# WiFiRadio.net
KiCad netlist of a schematic drawn in EAGLE
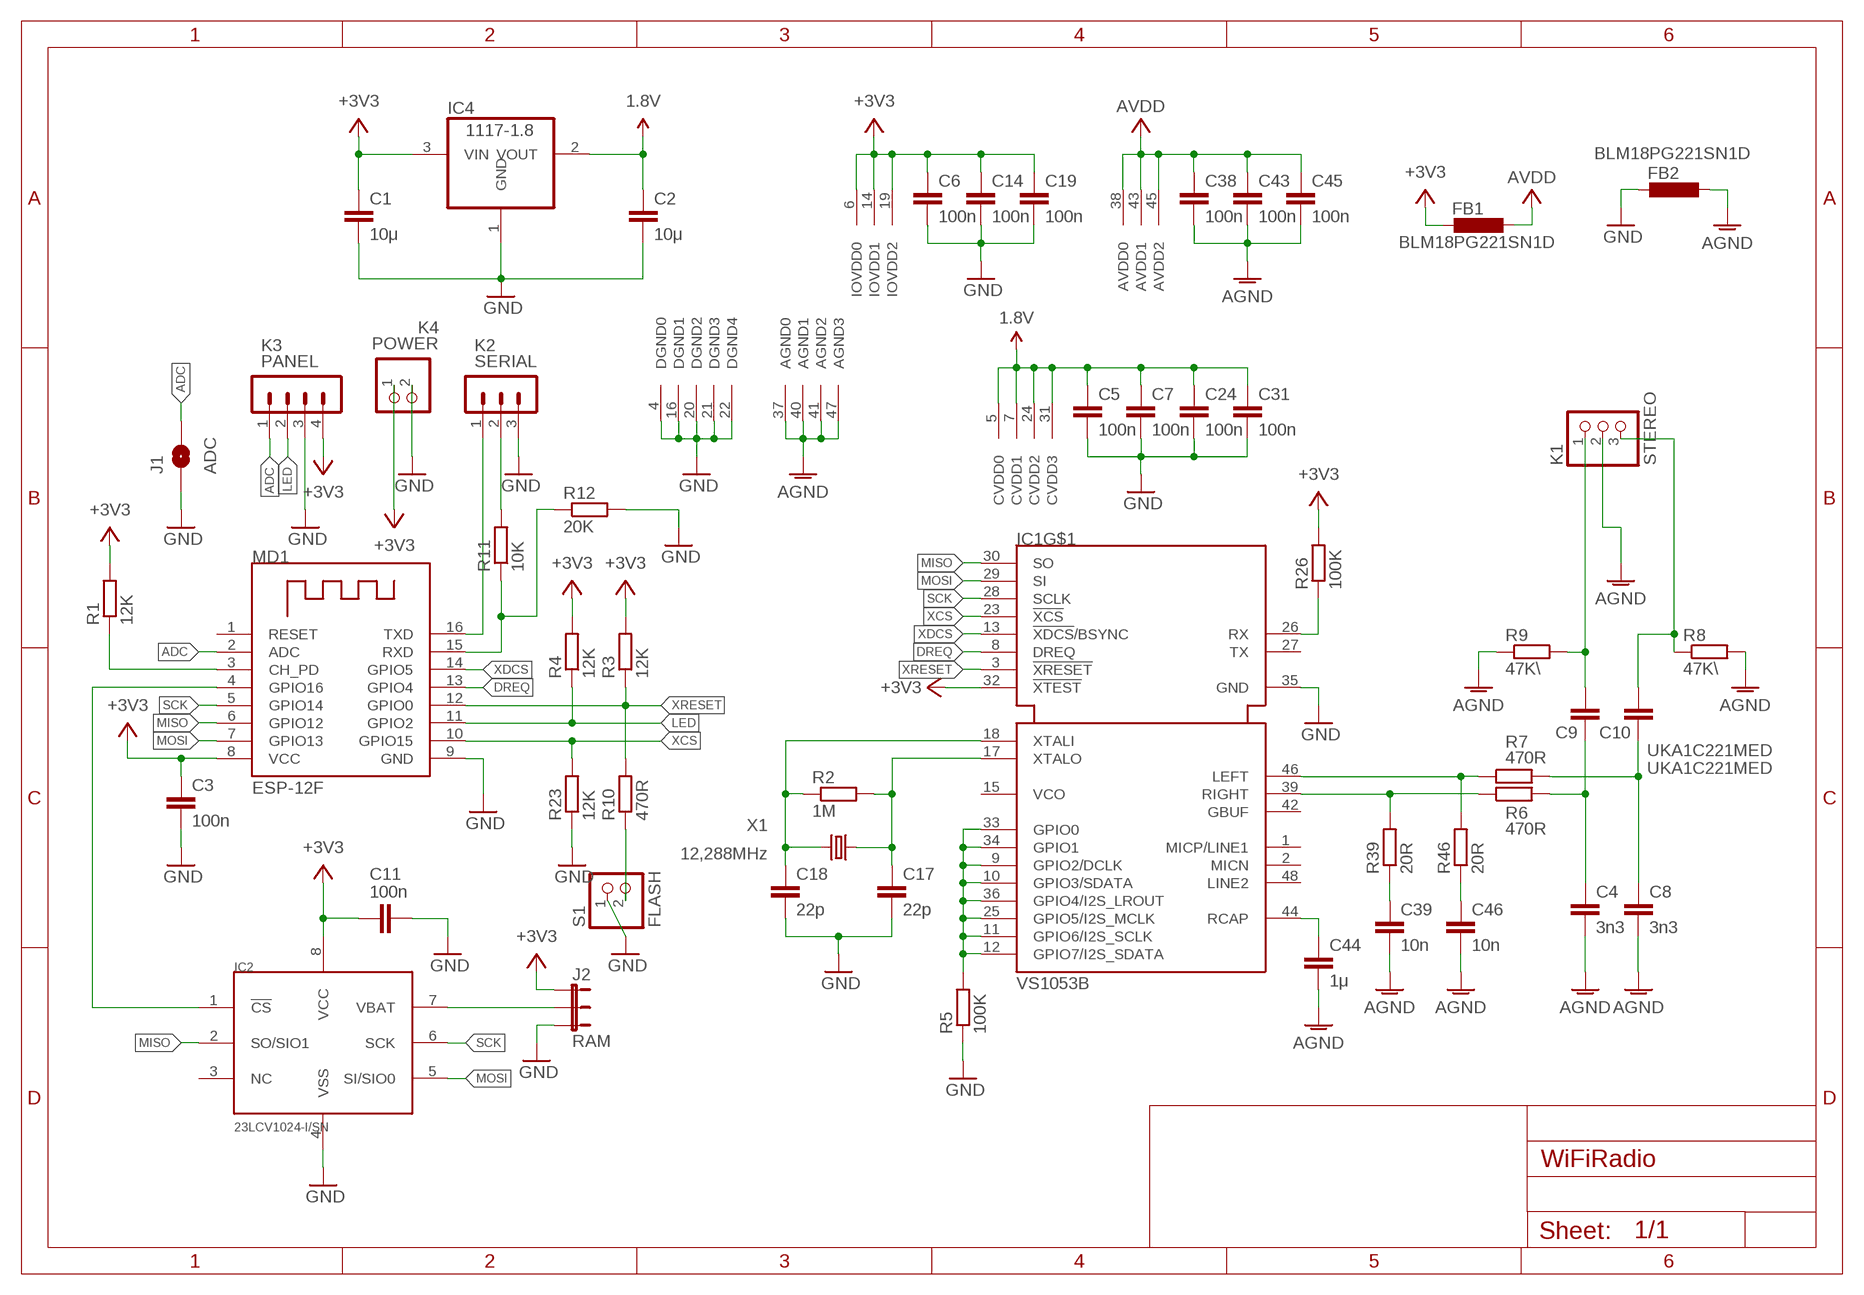
[diagram p0: schematic, sheet 1]

(export (version "E")
  (design (tool "Eeschema 10.0.6"))
  (components
    (comp (ref "C1")
      (value "10μ")
      (footprint "eagle-import:C0805")
      (libsource (lib "eagle-import") (part "C-EUC0805"))
    )
    (comp (ref "C2")
      (value "10μ")
      (footprint "eagle-import:C0805")
      (libsource (lib "eagle-import") (part "C-EUC0805"))
    )
    (comp (ref "C3")
      (value "100n")
      (footprint "eagle-import:C0603")
      (libsource (lib "eagle-import") (part "C-EUC0603"))
    )
    (comp (ref "C4")
      (value "3n3")
      (footprint "eagle-import:C0805")
      (libsource (lib "eagle-import") (part "C-EUC0805"))
    )
    (comp (ref "C5")
      (value "100n")
      (footprint "eagle-import:C0603")
      (libsource (lib "eagle-import") (part "C-EUC0603"))
    )
    (comp (ref "C6")
      (value "100n")
      (footprint "eagle-import:C0603")
      (libsource (lib "eagle-import") (part "C-EUC0603"))
    )
    (comp (ref "C7")
      (value "100n")
      (footprint "eagle-import:C0603")
      (libsource (lib "eagle-import") (part "C-EUC0603"))
    )
    (comp (ref "C8")
      (value "3n3")
      (footprint "eagle-import:C0805")
      (libsource (lib "eagle-import") (part "C-EUC0805"))
    )
    (comp (ref "C9")
      (value "UKA1C221MED")
      (footprint "eagle-import:C0805")
      (libsource (lib "eagle-import") (part "C-EUC0805"))
    )
    (comp (ref "C10")
      (value "UKA1C221MED")
      (footprint "eagle-import:C0805")
      (libsource (lib "eagle-import") (part "C-EUC0805"))
    )
    (comp (ref "C11")
      (value "100n")
      (footprint "eagle-import:C0603")
      (libsource (lib "eagle-import") (part "C-EUC0603"))
    )
    (comp (ref "C14")
      (value "100n")
      (footprint "eagle-import:C0603")
      (libsource (lib "eagle-import") (part "C-EUC0603"))
    )
    (comp (ref "C17")
      (value "22p")
      (footprint "eagle-import:C0805")
      (libsource (lib "eagle-import") (part "C-EUC0805"))
    )
    (comp (ref "C18")
      (value "22p")
      (footprint "eagle-import:C0805")
      (libsource (lib "eagle-import") (part "C-EUC0805"))
    )
    (comp (ref "C19")
      (value "100n")
      (footprint "eagle-import:C0603")
      (libsource (lib "eagle-import") (part "C-EUC0603"))
    )
    (comp (ref "C24")
      (value "100n")
      (footprint "eagle-import:C0603")
      (libsource (lib "eagle-import") (part "C-EUC0603"))
    )
    (comp (ref "C31")
      (value "100n")
      (footprint "eagle-import:C0603")
      (libsource (lib "eagle-import") (part "C-EUC0603"))
    )
    (comp (ref "C38")
      (value "100n")
      (footprint "eagle-import:C0603")
      (libsource (lib "eagle-import") (part "C-EUC0603"))
    )
    (comp (ref "C39")
      (value "10n")
      (footprint "eagle-import:C0805")
      (libsource (lib "eagle-import") (part "C-EUC0805"))
    )
    (comp (ref "C43")
      (value "100n")
      (footprint "eagle-import:C0603")
      (libsource (lib "eagle-import") (part "C-EUC0603"))
    )
    (comp (ref "C44")
      (value "1μ")
      (footprint "eagle-import:C0805")
      (libsource (lib "eagle-import") (part "C-EUC0805"))
    )
    (comp (ref "C45")
      (value "100n")
      (footprint "eagle-import:C0603")
      (libsource (lib "eagle-import") (part "C-EUC0603"))
    )
    (comp (ref "C46")
      (value "10n")
      (footprint "eagle-import:C0805")
      (libsource (lib "eagle-import") (part "C-EUC0805"))
    )
    (comp (ref "FB1")
      (value "BLM18PG221SN1D")
      (footprint "eagle-import:L2012C")
      (libsource (lib "eagle-import") (part "L-EUL2012C"))
    )
    (comp (ref "FB2")
      (value "BLM18PG221SN1D")
      (footprint "eagle-import:L2012C")
      (libsource (lib "eagle-import") (part "L-EUL2012C"))
    )
    (comp (ref "IC1")
      (value "VS1053B")
      (footprint "eagle-import:LQFP48")
      (libsource (lib "eagle-import") (part "VS1053B"))
    )
    (comp (ref "IC2")
      (value "23LCV1024-I/SN")
      (footprint "eagle-import:SO-08")
      (libsource (lib "eagle-import") (part "23LCV1024-I/SN"))
    )
    (comp (ref "IC4")
      (value "1117-1.8")
      (footprint "eagle-import:SOT223")
      (fields (field (name "MPN") "REG1117"))
      (libsource (lib "eagle-import") (part "REG1117"))
    )
    (comp (ref "J1")
      (value "ADC")
      (footprint "eagle-import:SJ_2S")
      (libsource (lib "eagle-import") (part "SOLDERJUMPER-OLDNC"))
    )
    (comp (ref "J2")
      (value "RAM")
      (footprint "eagle-import:SJ_3")
      (libsource (lib "eagle-import") (part "JUMPER-3SMD"))
    )
    (comp (ref "K1")
      (value "STEREO")
      (footprint "eagle-import:1X03")
      (libsource (lib "eagle-import") (part "PINHD-1X3"))
    )
    (comp (ref "K2")
      (value "SERIAL")
      (footprint "eagle-import:MA03-1")
      (libsource (lib "eagle-import") (part "MA03-1"))
    )
    (comp (ref "K3")
      (value "PANEL")
      (footprint "eagle-import:MA04-1")
      (libsource (lib "eagle-import") (part "MA04-1"))
    )
    (comp (ref "K4")
      (value "POWER")
      (footprint "eagle-import:1X02")
      (libsource (lib "eagle-import") (part "PINHD-1X2"))
    )
    (comp (ref "MD1")
      (value "ESP-12F")
      (footprint "eagle-import:ESP-12F")
      (libsource (lib "eagle-import") (part "ESP-12F"))
    )
    (comp (ref "R1")
      (value "12K")
      (footprint "eagle-import:R0805")
      (libsource (lib "eagle-import") (part "R-EU_R0805"))
    )
    (comp (ref "R2")
      (value "1M")
      (footprint "eagle-import:R0805")
      (libsource (lib "eagle-import") (part "R-EU_R0805"))
    )
    (comp (ref "R3")
      (value "12K")
      (footprint "eagle-import:R0805")
      (libsource (lib "eagle-import") (part "R-EU_R0805"))
    )
    (comp (ref "R4")
      (value "12K")
      (footprint "eagle-import:R0805")
      (libsource (lib "eagle-import") (part "R-EU_R0805"))
    )
    (comp (ref "R5")
      (value "100K")
      (footprint "eagle-import:R0805")
      (libsource (lib "eagle-import") (part "R-EU_R0805"))
    )
    (comp (ref "R6")
      (value "470R")
      (footprint "eagle-import:R0805")
      (libsource (lib "eagle-import") (part "R-EU_R0805"))
    )
    (comp (ref "R7")
      (value "470R")
      (footprint "eagle-import:R0805")
      (libsource (lib "eagle-import") (part "R-EU_R0805"))
    )
    (comp (ref "R8")
      (value "47K\\")
      (footprint "eagle-import:R0805")
      (libsource (lib "eagle-import") (part "R-EU_R0805"))
    )
    (comp (ref "R9")
      (value "47K\\")
      (footprint "eagle-import:R0805")
      (libsource (lib "eagle-import") (part "R-EU_R0805"))
    )
    (comp (ref "R10")
      (value "470R")
      (footprint "eagle-import:R0805")
      (libsource (lib "eagle-import") (part "R-EU_R0805"))
    )
    (comp (ref "R11")
      (value "10K")
      (footprint "eagle-import:R0603")
      (libsource (lib "eagle-import") (part "R-EU_R0603"))
    )
    (comp (ref "R12")
      (value "20K")
      (footprint "eagle-import:R0603")
      (libsource (lib "eagle-import") (part "R-EU_R0603"))
    )
    (comp (ref "R23")
      (value "12K")
      (footprint "eagle-import:R0805")
      (libsource (lib "eagle-import") (part "R-EU_R0805"))
    )
    (comp (ref "R26")
      (value "100K")
      (footprint "eagle-import:R0805")
      (libsource (lib "eagle-import") (part "R-EU_R0805"))
    )
    (comp (ref "R39")
      (value "20R")
      (footprint "eagle-import:R0805")
      (libsource (lib "eagle-import") (part "R-EU_R0805"))
    )
    (comp (ref "R46")
      (value "20R")
      (footprint "eagle-import:R0805")
      (libsource (lib "eagle-import") (part "R-EU_R0805"))
    )
    (comp (ref "S1")
      (value "FLASH")
      (footprint "eagle-import:1X02")
      (libsource (lib "eagle-import") (part "PINHD-1X2"))
    )
    (comp (ref "X1")
      (value "12,288MHz")
      (footprint "eagle-import:HC49_S")
      (libsource (lib "eagle-import") (part "CRYSTALHC49S"))
    )
  )
  (nets
    (net (code "1") (name "+3V3") (class "Default")
      (node (ref "C1") (pin "1") (pinfunction "1_1") (pintype "passive"))
      (node (ref "C11") (pin "1") (pinfunction "1_1") (pintype "passive"))
      (node (ref "C14") (pin "1") (pinfunction "1_1") (pintype "passive"))
      (node (ref "C19") (pin "1") (pinfunction "1_1") (pintype "passive"))
      (node (ref "C3") (pin "1") (pinfunction "1_1") (pintype "passive"))
      (node (ref "C6") (pin "1") (pinfunction "1_1") (pintype "passive"))
      (node (ref "FB1") (pin "2") (pinfunction "2_2") (pintype "passive"))
      (node (ref "IC1") (pin "14") (pinfunction "IOVDD1_14") (pintype "power_in"))
      (node (ref "IC1") (pin "19") (pinfunction "IOVDD2_19") (pintype "power_in"))
      (node (ref "IC1") (pin "32") (pinfunction "~{XTEST}_32") (pintype "input"))
      (node (ref "IC1") (pin "6") (pinfunction "IOVDD0_6") (pintype "power_in"))
      (node (ref "IC2") (pin "8") (pinfunction "VCC_8") (pintype "power_in"))
      (node (ref "IC4") (pin "3") (pinfunction "VIN_3") (pintype "input"))
      (node (ref "J2") (pin "1") (pinfunction "1_1") (pintype "passive"))
      (node (ref "K3") (pin "4") (pinfunction "4_4") (pintype "passive"))
      (node (ref "K4") (pin "1") (pinfunction "1_1") (pintype "passive"))
      (node (ref "MD1") (pin "8") (pinfunction "VCC_8") (pintype "power_in"))
      (node (ref "R1") (pin "2") (pinfunction "2_2") (pintype "passive"))
      (node (ref "R26") (pin "2") (pinfunction "2_2") (pintype "passive"))
      (node (ref "R3") (pin "2") (pinfunction "2_2") (pintype "passive"))
      (node (ref "R4") (pin "2") (pinfunction "2_2") (pintype "passive"))
    )
    (net (code "2") (name "1.8V") (class "Default")
      (node (ref "C2") (pin "1") (pinfunction "1_1") (pintype "passive"))
      (node (ref "C24") (pin "1") (pinfunction "1_1") (pintype "passive"))
      (node (ref "C31") (pin "1") (pinfunction "1_1") (pintype "passive"))
      (node (ref "C5") (pin "1") (pinfunction "1_1") (pintype "passive"))
      (node (ref "C7") (pin "1") (pinfunction "1_1") (pintype "passive"))
      (node (ref "IC1") (pin "24") (pinfunction "CVDD2_24") (pintype "power_in"))
      (node (ref "IC1") (pin "31") (pinfunction "CVDD3_31") (pintype "power_in"))
      (node (ref "IC1") (pin "5") (pinfunction "CVDD0_5") (pintype "power_in"))
      (node (ref "IC1") (pin "7") (pinfunction "CVDD1_7") (pintype "power_in"))
      (node (ref "IC4") (pin "2") (pinfunction "VOUT_2") (pintype "output"))
    )
    (net (code "3") (name "ADC") (class "Default")
      (node (ref "J1") (pin "2") (pinfunction "2_2") (pintype "passive"))
      (node (ref "K3") (pin "1") (pinfunction "1_1") (pintype "passive"))
      (node (ref "MD1") (pin "2") (pinfunction "ADC_2") (pintype "passive"))
    )
    (net (code "4") (name "AGND") (class "Default")
      (node (ref "C38") (pin "2") (pinfunction "2_2") (pintype "passive"))
      (node (ref "C39") (pin "2") (pinfunction "2_2") (pintype "passive"))
      (node (ref "C4") (pin "2") (pinfunction "2_2") (pintype "passive"))
      (node (ref "C43") (pin "2") (pinfunction "2_2") (pintype "passive"))
      (node (ref "C44") (pin "2") (pinfunction "2_2") (pintype "passive"))
      (node (ref "C45") (pin "2") (pinfunction "2_2") (pintype "passive"))
      (node (ref "C46") (pin "2") (pinfunction "2_2") (pintype "passive"))
      (node (ref "C8") (pin "2") (pinfunction "2_2") (pintype "passive"))
      (node (ref "FB2") (pin "1") (pinfunction "1_1") (pintype "passive"))
      (node (ref "IC1") (pin "37") (pinfunction "AGND0_37") (pintype "power_in"))
      (node (ref "IC1") (pin "40") (pinfunction "AGND1_40") (pintype "power_in"))
      (node (ref "IC1") (pin "41") (pinfunction "AGND2_41") (pintype "power_in"))
      (node (ref "IC1") (pin "47") (pinfunction "AGND3_47") (pintype "power_in"))
      (node (ref "K1") (pin "2") (pinfunction "2_2") (pintype "passive"))
      (node (ref "R8") (pin "2") (pinfunction "2_2") (pintype "passive"))
      (node (ref "R9") (pin "1") (pinfunction "1_1") (pintype "passive"))
    )
    (net (code "5") (name "AVDD") (class "Default")
      (node (ref "C38") (pin "1") (pinfunction "1_1") (pintype "passive"))
      (node (ref "C43") (pin "1") (pinfunction "1_1") (pintype "passive"))
      (node (ref "C45") (pin "1") (pinfunction "1_1") (pintype "passive"))
      (node (ref "FB1") (pin "1") (pinfunction "1_1") (pintype "passive"))
      (node (ref "IC1") (pin "38") (pinfunction "AVDD0_38") (pintype "power_in"))
      (node (ref "IC1") (pin "43") (pinfunction "AVDD1_43") (pintype "power_in"))
      (node (ref "IC1") (pin "45") (pinfunction "AVDD2_45") (pintype "power_in"))
    )
    (net (code "6") (name "DREQ") (class "Default")
      (node (ref "IC1") (pin "8") (pinfunction "DREQ_8") (pintype "output"))
      (node (ref "MD1") (pin "13") (pinfunction "GPIO4_13") (pintype "bidirectional"))
    )
    (net (code "7") (name "GND") (class "Default")
      (node (ref "C1") (pin "2") (pinfunction "2_2") (pintype "passive"))
      (node (ref "C11") (pin "2") (pinfunction "2_2") (pintype "passive"))
      (node (ref "C14") (pin "2") (pinfunction "2_2") (pintype "passive"))
      (node (ref "C17") (pin "2") (pinfunction "2_2") (pintype "passive"))
      (node (ref "C18") (pin "2") (pinfunction "2_2") (pintype "passive"))
      (node (ref "C19") (pin "2") (pinfunction "2_2") (pintype "passive"))
      (node (ref "C2") (pin "2") (pinfunction "2_2") (pintype "passive"))
      (node (ref "C24") (pin "2") (pinfunction "2_2") (pintype "passive"))
      (node (ref "C3") (pin "2") (pinfunction "2_2") (pintype "passive"))
      (node (ref "C31") (pin "2") (pinfunction "2_2") (pintype "passive"))
      (node (ref "C5") (pin "2") (pinfunction "2_2") (pintype "passive"))
      (node (ref "C6") (pin "2") (pinfunction "2_2") (pintype "passive"))
      (node (ref "C7") (pin "2") (pinfunction "2_2") (pintype "passive"))
      (node (ref "FB2") (pin "2") (pinfunction "2_2") (pintype "passive"))
      (node (ref "IC1") (pin "16") (pinfunction "DGND1_16") (pintype "power_in"))
      (node (ref "IC1") (pin "20") (pinfunction "DGND2_20") (pintype "power_in"))
      (node (ref "IC1") (pin "21") (pinfunction "DGND3_21") (pintype "power_in"))
      (node (ref "IC1") (pin "22") (pinfunction "DGND4_22") (pintype "power_in"))
      (node (ref "IC1") (pin "35") (pinfunction "GND_35") (pintype "power_in"))
      (node (ref "IC1") (pin "4") (pinfunction "DGND0_4") (pintype "power_in"))
      (node (ref "IC2") (pin "4") (pinfunction "VSS_4") (pintype "power_in"))
      (node (ref "IC4") (pin "1") (pinfunction "GND_1") (pintype "power_in"))
      (node (ref "J1") (pin "1") (pinfunction "1_1") (pintype "passive"))
      (node (ref "J2") (pin "3") (pinfunction "3_3") (pintype "passive"))
      (node (ref "K2") (pin "3") (pinfunction "3_3") (pintype "passive"))
      (node (ref "K3") (pin "3") (pinfunction "3_3") (pintype "passive"))
      (node (ref "K4") (pin "2") (pinfunction "2_2") (pintype "passive"))
      (node (ref "MD1") (pin "9") (pinfunction "GND_9") (pintype "power_in"))
      (node (ref "R12") (pin "2") (pinfunction "2_2") (pintype "passive"))
      (node (ref "R23") (pin "1") (pinfunction "1_1") (pintype "passive"))
      (node (ref "R5") (pin "1") (pinfunction "1_1") (pintype "passive"))
      (node (ref "S1") (pin "1") (pinfunction "1_1") (pintype "passive"))
    )
    (net (code "8") (name "LED") (class "Default")
      (node (ref "K3") (pin "2") (pinfunction "2_2") (pintype "passive"))
      (node (ref "MD1") (pin "11") (pinfunction "GPIO2_11") (pintype "bidirectional"))
      (node (ref "R4") (pin "1") (pinfunction "1_1") (pintype "passive"))
    )
    (net (code "9") (name "MISO") (class "Default")
      (node (ref "IC1") (pin "30") (pinfunction "SO_30") (pintype "output"))
      (node (ref "IC2") (pin "2") (pinfunction "SO/SIO1_2") (pintype "bidirectional"))
      (node (ref "MD1") (pin "6") (pinfunction "GPIO12_6") (pintype "bidirectional"))
    )
    (net (code "10") (name "MOSI") (class "Default")
      (node (ref "IC1") (pin "29") (pinfunction "SI_29") (pintype "input"))
      (node (ref "IC2") (pin "5") (pinfunction "SI/SIO0_5") (pintype "bidirectional"))
      (node (ref "MD1") (pin "7") (pinfunction "GPIO13_7") (pintype "bidirectional"))
    )
    (net (code "11") (name "Net-(C4-Pad1)") (class "Default")
      (node (ref "C4") (pin "1") (pinfunction "1_1") (pintype "passive"))
      (node (ref "C9") (pin "1") (pinfunction "1_1") (pintype "passive"))
      (node (ref "R6") (pin "2") (pinfunction "2_2") (pintype "passive"))
    )
    (net (code "12") (name "Net-(C9-Pad2)") (class "Default")
      (node (ref "C9") (pin "2") (pinfunction "2_2") (pintype "passive"))
      (node (ref "K1") (pin "1") (pinfunction "1_1") (pintype "passive"))
      (node (ref "R9") (pin "2") (pinfunction "2_2") (pintype "passive"))
    )
    (net (code "13") (name "Net-(C10-Pad1)") (class "Default")
      (node (ref "C10") (pin "1") (pinfunction "1_1") (pintype "passive"))
      (node (ref "C8") (pin "1") (pinfunction "1_1") (pintype "passive"))
      (node (ref "R7") (pin "2") (pinfunction "2_2") (pintype "passive"))
    )
    (net (code "14") (name "Net-(C10-Pad2)") (class "Default")
      (node (ref "C10") (pin "2") (pinfunction "2_2") (pintype "passive"))
      (node (ref "K1") (pin "3") (pinfunction "3_3") (pintype "passive"))
      (node (ref "R8") (pin "1") (pinfunction "1_1") (pintype "passive"))
    )
    (net (code "15") (name "Net-(C39-Pad1)") (class "Default")
      (node (ref "C39") (pin "1") (pinfunction "1_1") (pintype "passive"))
      (node (ref "R39") (pin "1") (pinfunction "1_1") (pintype "passive"))
    )
    (net (code "16") (name "Net-(C46-Pad1)") (class "Default")
      (node (ref "C46") (pin "1") (pinfunction "1_1") (pintype "passive"))
      (node (ref "R46") (pin "1") (pinfunction "1_1") (pintype "passive"))
    )
    (net (code "17") (name "Net-(IC1A-GPIO0)") (class "Default")
      (node (ref "IC1") (pin "10") (pinfunction "GPIO3/SDATA_10") (pintype "bidirectional"))
      (node (ref "IC1") (pin "11") (pinfunction "GPIO6/I2S_SCLK_11") (pintype "bidirectional"))
      (node (ref "IC1") (pin "12") (pinfunction "GPIO7/I2S_SDATA_12") (pintype "bidirectional"))
      (node (ref "IC1") (pin "25") (pinfunction "GPIO5/I2S_MCLK_25") (pintype "bidirectional"))
      (node (ref "IC1") (pin "33") (pinfunction "GPIO0_33") (pintype "bidirectional"))
      (node (ref "IC1") (pin "34") (pinfunction "GPIO1_34") (pintype "bidirectional"))
      (node (ref "IC1") (pin "36") (pinfunction "GPIO4/I2S_LROUT_36") (pintype "bidirectional"))
      (node (ref "IC1") (pin "9") (pinfunction "GPIO2/DCLK_9") (pintype "bidirectional"))
      (node (ref "R5") (pin "2") (pinfunction "2_2") (pintype "passive"))
    )
    (net (code "18") (name "Net-(IC1A-LEFT)") (class "Default")
      (node (ref "IC1") (pin "46") (pinfunction "LEFT_46") (pintype "output"))
      (node (ref "R46") (pin "2") (pinfunction "2_2") (pintype "passive"))
      (node (ref "R7") (pin "1") (pinfunction "1_1") (pintype "passive"))
    )
    (net (code "19") (name "Net-(IC1A-RCAP)") (class "Default")
      (node (ref "C44") (pin "1") (pinfunction "1_1") (pintype "passive"))
      (node (ref "IC1") (pin "44") (pinfunction "RCAP_44") (pintype "bidirectional"))
    )
    (net (code "20") (name "Net-(IC1A-RIGHT)") (class "Default")
      (node (ref "IC1") (pin "39") (pinfunction "RIGHT_39") (pintype "output"))
      (node (ref "R39") (pin "2") (pinfunction "2_2") (pintype "passive"))
      (node (ref "R6") (pin "1") (pinfunction "1_1") (pintype "passive"))
    )
    (net (code "21") (name "Net-(IC1A-RX)") (class "Default")
      (node (ref "IC1") (pin "26") (pinfunction "RX_26") (pintype "input"))
      (node (ref "R26") (pin "1") (pinfunction "1_1") (pintype "passive"))
    )
    (net (code "22") (name "Net-(IC1A-XTALI)") (class "Default")
      (node (ref "C18") (pin "1") (pinfunction "1_1") (pintype "passive"))
      (node (ref "IC1") (pin "18") (pinfunction "XTALI_18") (pintype "input"))
      (node (ref "R2") (pin "1") (pinfunction "1_1") (pintype "passive"))
      (node (ref "X1") (pin "2") (pinfunction "2_2") (pintype "passive"))
    )
    (net (code "23") (name "Net-(IC1A-XTALO)") (class "Default")
      (node (ref "C17") (pin "1") (pinfunction "1_1") (pintype "passive"))
      (node (ref "IC1") (pin "17") (pinfunction "XTALO_17") (pintype "output"))
      (node (ref "R2") (pin "2") (pinfunction "2_2") (pintype "passive"))
      (node (ref "X1") (pin "1") (pinfunction "1_1") (pintype "passive"))
    )
    (net (code "24") (name "Net-(IC2-VBAT)") (class "Default")
      (node (ref "IC2") (pin "7") (pinfunction "VBAT_7") (pintype "power_in"))
      (node (ref "J2") (pin "2") (pinfunction "2_2") (pintype "passive"))
    )
    (net (code "25") (name "Net-(IC2-~{CS})") (class "Default")
      (node (ref "IC2") (pin "1") (pinfunction "~{CS}_1") (pintype "input"))
      (node (ref "MD1") (pin "4") (pinfunction "GPIO16_4") (pintype "bidirectional"))
    )
    (net (code "26") (name "Net-(K2-Pad2)") (class "Default")
      (node (ref "K2") (pin "2") (pinfunction "2_2") (pintype "passive"))
      (node (ref "R11") (pin "2") (pinfunction "2_2") (pintype "passive"))
    )
    (net (code "27") (name "Net-(MD1-CH_PD)") (class "Default")
      (node (ref "MD1") (pin "3") (pinfunction "CH_PD_3") (pintype "input"))
      (node (ref "R1") (pin "1") (pinfunction "1_1") (pintype "passive"))
    )
    (net (code "28") (name "Net-(MD1-RXD)") (class "Default")
      (node (ref "MD1") (pin "15") (pinfunction "RXD_15") (pintype "input"))
      (node (ref "R11") (pin "1") (pinfunction "1_1") (pintype "passive"))
      (node (ref "R12") (pin "1") (pinfunction "1_1") (pintype "passive"))
    )
    (net (code "29") (name "Net-(MD1-TXD)") (class "Default")
      (node (ref "K2") (pin "1") (pinfunction "1_1") (pintype "passive"))
      (node (ref "MD1") (pin "16") (pinfunction "TXD_16") (pintype "output"))
    )
    (net (code "30") (name "Net-(R10-Pad1)") (class "Default")
      (node (ref "R10") (pin "1") (pinfunction "1_1") (pintype "passive"))
      (node (ref "S1") (pin "2") (pinfunction "2_2") (pintype "passive"))
    )
    (net (code "31") (name "SCK") (class "Default")
      (node (ref "IC1") (pin "28") (pinfunction "SCLK_28") (pintype "input"))
      (node (ref "IC2") (pin "6") (pinfunction "SCK_6") (pintype "input"))
      (node (ref "MD1") (pin "5") (pinfunction "GPIO14_5") (pintype "bidirectional"))
    )
    (net (code "32") (name "XCS") (class "Default")
      (node (ref "IC1") (pin "23") (pinfunction "~{XCS}_23") (pintype "input"))
      (node (ref "MD1") (pin "10") (pinfunction "GPIO15_10") (pintype "bidirectional"))
      (node (ref "R23") (pin "2") (pinfunction "2_2") (pintype "passive"))
    )
    (net (code "33") (name "XDCS") (class "Default")
      (node (ref "IC1") (pin "13") (pinfunction "~{XDCS}/BSYNC_13") (pintype "input"))
      (node (ref "MD1") (pin "14") (pinfunction "GPIO5_14") (pintype "bidirectional"))
    )
    (net (code "34") (name "XRESET") (class "Default")
      (node (ref "IC1") (pin "3") (pinfunction "~{XRESET}_3") (pintype "input"))
      (node (ref "MD1") (pin "12") (pinfunction "GPIO0_12") (pintype "bidirectional"))
      (node (ref "R10") (pin "2") (pinfunction "2_2") (pintype "passive"))
      (node (ref "R3") (pin "1") (pinfunction "1_1") (pintype "passive"))
    )
    (net (code "35") (name "unconnected-(IC1A-GBUF-Pad42)") (class "Default")
      (node (ref "IC1") (pin "42") (pinfunction "GBUF_42") (pintype "output"))
    )
    (net (code "36") (name "unconnected-(IC1A-LINE2-Pad48)") (class "Default")
      (node (ref "IC1") (pin "48") (pinfunction "LINE2_48") (pintype "input"))
    )
    (net (code "37") (name "unconnected-(IC1A-MICN-Pad2)") (class "Default")
      (node (ref "IC1") (pin "2") (pinfunction "MICN_2") (pintype "input"))
    )
    (net (code "38") (name "unconnected-(IC1A-MICP{slash}LINE1-Pad1)") (class "Default")
      (node (ref "IC1") (pin "1") (pinfunction "MICP/LINE1_1") (pintype "input"))
    )
    (net (code "39") (name "unconnected-(IC1A-TX-Pad27)") (class "Default")
      (node (ref "IC1") (pin "27") (pinfunction "TX_27") (pintype "output"))
    )
    (net (code "40") (name "unconnected-(IC1A-VCO-Pad15)") (class "Default")
      (node (ref "IC1") (pin "15") (pinfunction "VCO_15") (pintype "output"))
    )
    (net (code "41") (name "unconnected-(IC2-NC-Pad3)") (class "Default")
      (node (ref "IC2") (pin "3") (pinfunction "NC_3") (pintype "no_connect"))
    )
    (net (code "42") (name "unconnected-(MD1-RESET-Pad1)") (class "Default")
      (node (ref "MD1") (pin "1") (pinfunction "RESET_1") (pintype "input"))
    )
  )
)
